# MAIN.net
KiCad netlist of a schematic drawn in Altium Designer
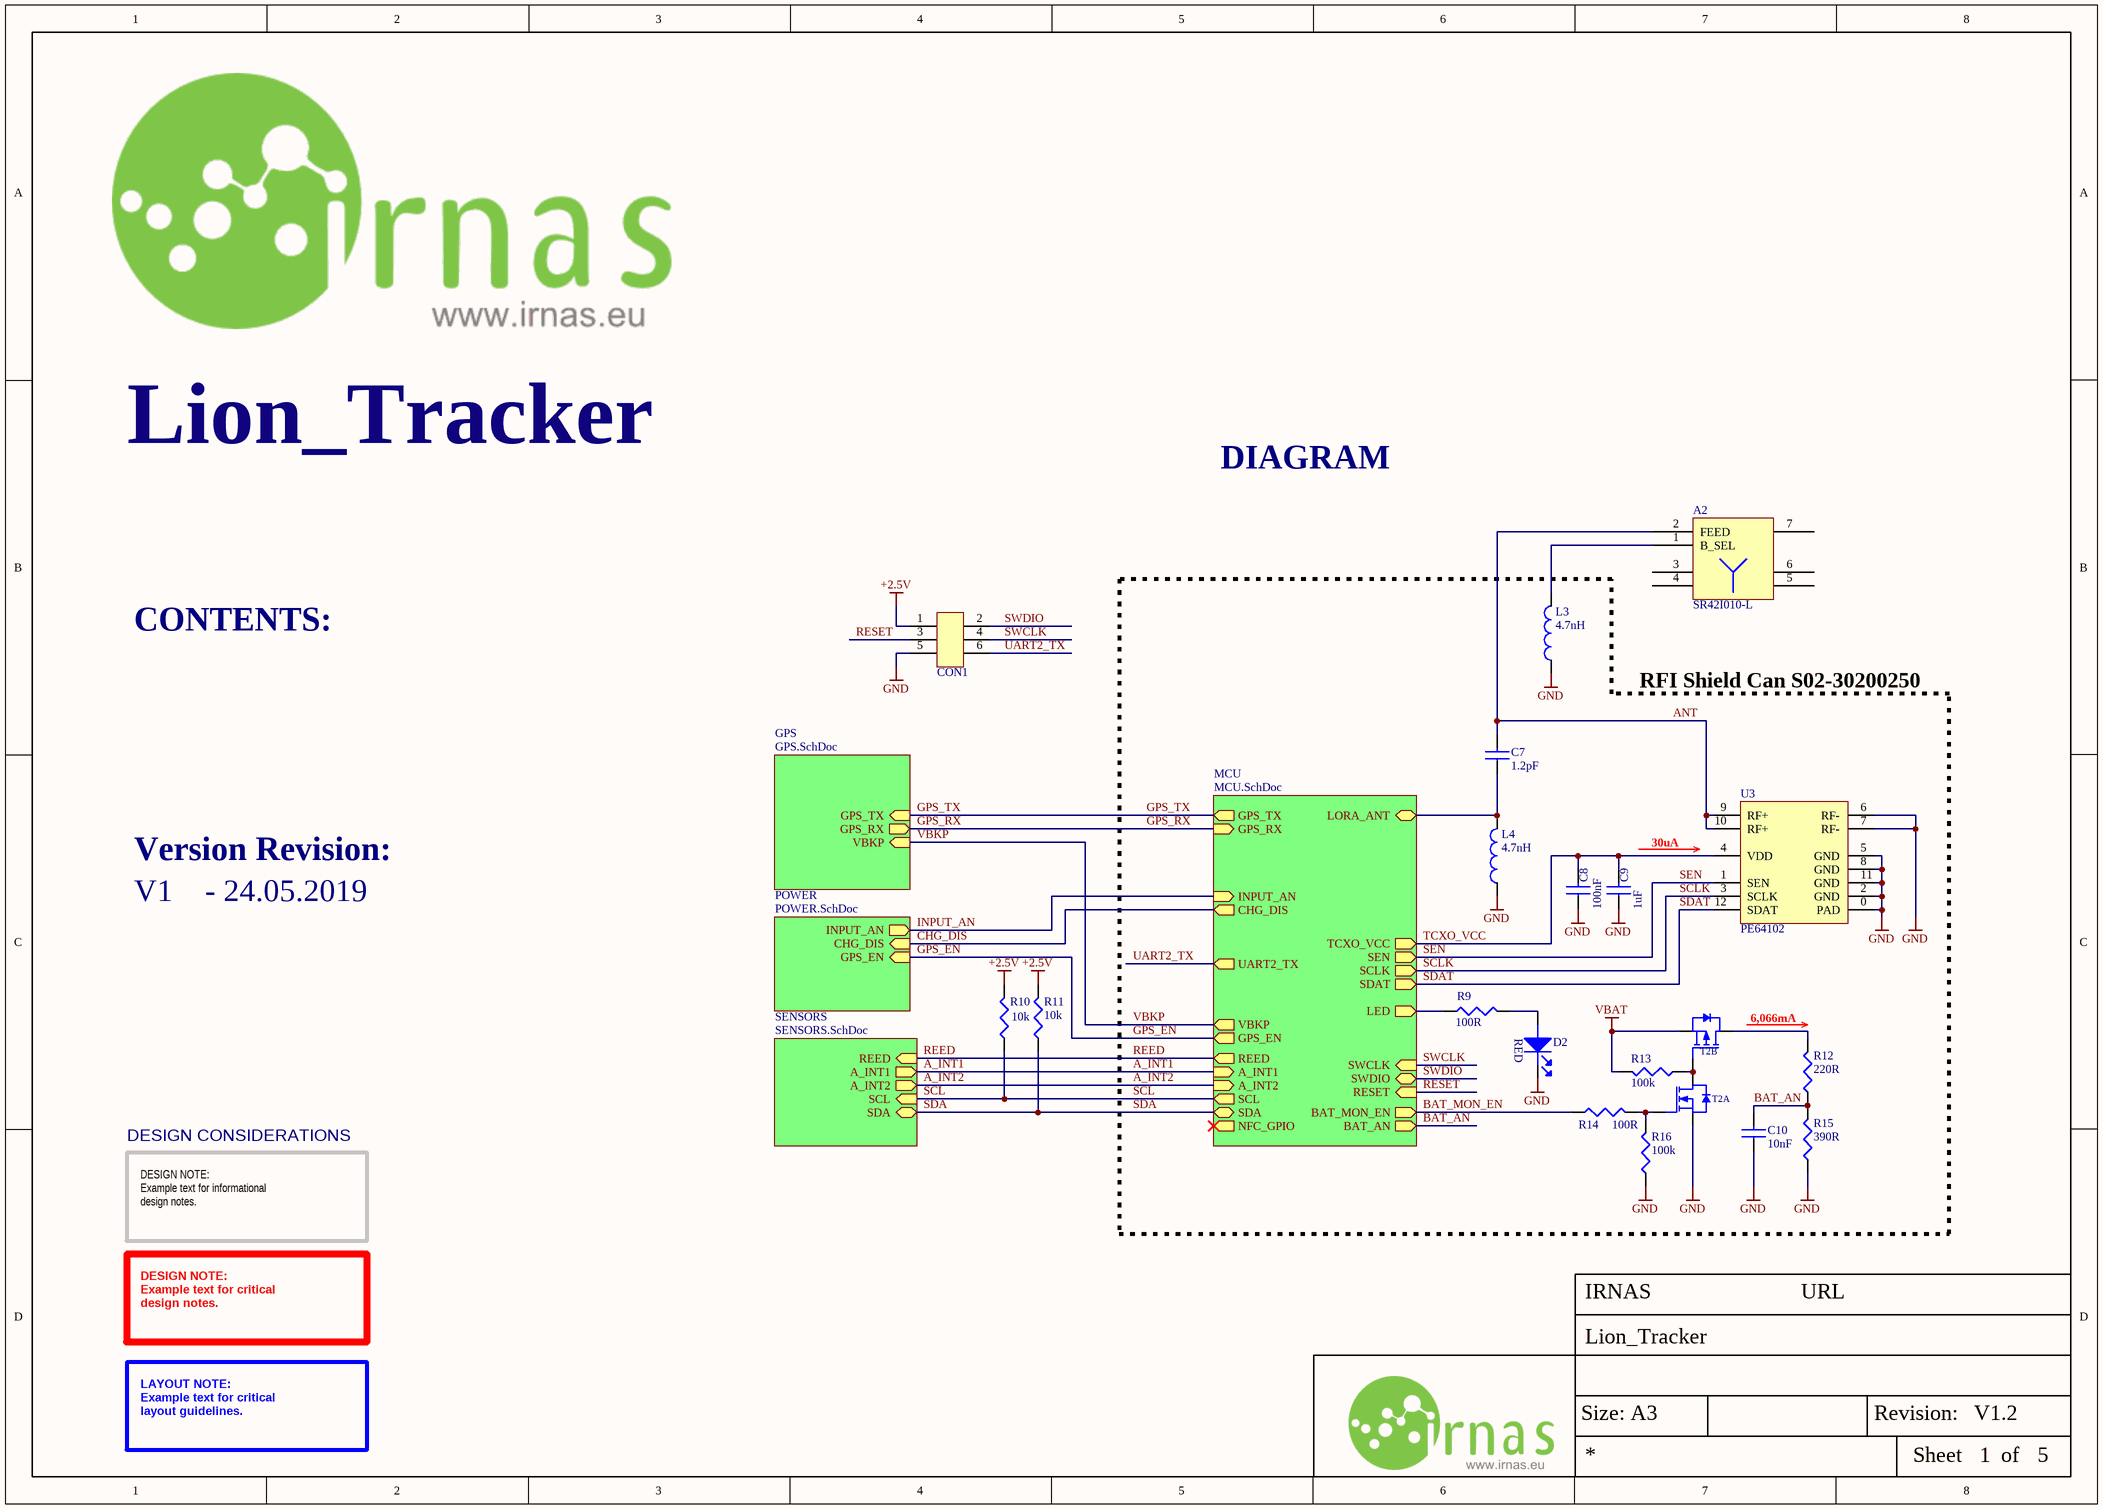
[diagram p0: MAIN.SchDoc]

(export (version "E")
  (design (tool "Eeschema 10.0.6"))
  (components
    (comp (ref "A2")
      (value "SR42I010-L")
      (footprint "SR42I010-L")
      (description "Antenna SMD -4dBi Gain 870MHz/928MHz Automotive 7-Pin SMD T/R")
      (fields (field (name "MANUFACTURER") "Antenova") (field (name "MANUFACTURER PART NUMBER") "SR42I010-R"))
      (libsource (lib "Passive") (part "ANT - SR42I010-L"))
    )
    (comp (ref "C7")
      (value "1.2pF")
      (footprint "CAP0402")
      (description "CAP CER 4700PF 50V X7R 0402")
      (fields
        (field (name "MANUFACTURER") "KEMET")
        (field (name "MANUFACTURER PART NUMBER") "C0402C472K5RAC-TU")
      )
      (libsource (lib "Passive") (part "C - 4.7nF/0402"))
    )
    (comp (ref "C8")
      (value "100nF")
      (footprint "CAP0402")
      (fields
        (field (name "MANUFACTURER") "Multicomp")
        (field (name "MANUFACTURER PART NUMBER") "MC0402X104J160CT")
        (field (name "TOLERANCE") "5%")
      )
      (libsource (lib "Passive") (part "C - 100nF/0402"))
    )
    (comp (ref "C9")
      (value "1uF")
      (footprint "CAP0402")
      (description "CAP CER 1UF 10V 20% X5R 0402")
      (fields
        (field (name "MANUFACTURER") "Murata")
        (field (name "MANUFACTURER PART NUMBER") "GRM155R61A105ME15D")
      )
      (libsource (lib "Passive") (part "C - 1uF/0402"))
    )
    (comp (ref "C10")
      (value "10nF")
      (footprint "CAP0402")
      (description "CAP CER 10000PF 16V X7R 0402")
      (fields
        (field (name "MANUFACTURER") "Murata")
        (field (name "MANUFACTURER PART NUMBER") "GRM155R71C103KA01D")
      )
      (libsource (lib "Passive") (part "C - 10nF/0402"))
    )
    (comp (ref "CON1")
      (value "Tag connect")
      (footprint "TC2030-IDC-NL")
      (libsource (lib "Connectors") (part "tag connecot 6 pin"))
    )
    (comp (ref "D2")
      (value "LED RED")
      (footprint "LED0603")
      (description "BROADCOM LIMITED - HSMS-C190 - LED, RED, 10MCD, 626NM")
      (fields
        (field (name "MANUFACTURER") "BROADCOM LIMITED")
        (field (name "MANUFACTURER PART NUMBER") "HSMS-C190")
      )
      (libsource (lib "Active") (part "LED - LED RED"))
    )
    (comp (ref "L3")
      (value "4.7nH")
      (footprint "IND0402")
      (description "Inductor RF Chip Multi-Layer 4.3nH 0.3nH 100MHz 8Q-Factor Air 300mA 210mOhm DCR 0402 Paper T/R")
      (fields
        (field (name "MANUFACTURER") "Murata")
        (field (name "MANUFACTURER PART NUMBER") "LQG15HN4N3S02D")
      )
      (libsource (lib "Passive") (part "L - 4.3nH/0402"))
    )
    (comp (ref "L4")
      (value "4.7nH")
      (footprint "IND0402")
      (description "Inductor RF Chip Multi-Layer 4.3nH 0.3nH 100MHz 8Q-Factor Air 300mA 210mOhm DCR 0402 Paper T/R")
      (fields
        (field (name "MANUFACTURER") "Murata")
        (field (name "MANUFACTURER PART NUMBER") "LQG15HN4N3S02D")
      )
      (libsource (lib "Passive") (part "L - 4.3nH/0402"))
    )
    (comp (ref "R9")
      (value "100R")
      (footprint "RES0402")
      (fields
        (field (name "MANUFACTURER") "Multicomp")
        (field (name "MANUFACTURER PART NUMBER") "MCMR04X1000FTL")
        (field (name "TOLERANCE") "1%")
      )
      (libsource (lib "Passive") (part "R - 100R/0402"))
    )
    (comp (ref "R10")
      (value "10k")
      (footprint "RES0402")
      (fields
        (field (name "MANUFACTURER") "Multicomp")
        (field (name "MANUFACTURER PART NUMBER") "MCWR04X1002FTL")
        (field (name "TOLERANCE") "1%")
      )
      (libsource (lib "Passive") (part "R - 10k/0402"))
    )
    (comp (ref "R11")
      (value "10k")
      (footprint "RES0402")
      (fields
        (field (name "MANUFACTURER") "Multicomp")
        (field (name "MANUFACTURER PART NUMBER") "MCWR04X1002FTL")
        (field (name "TOLERANCE") "1%")
      )
      (libsource (lib "Passive") (part "R - 10k/0402"))
    )
    (comp (ref "R12")
      (value "220R")
      (footprint "RES0402")
      (description "SMD Chip Resistor, 0402 [1005 Metric], 220 ohm, CRCW e3 Series, 50 V, Thick Film, 63 mW")
      (fields (field (name "MANUFACTURER") "Multicomp") (field (name "IRNAS PART NO.") "/"))
      (libsource (lib "Passive") (part "R - 220R/0402"))
    )
    (comp (ref "R13")
      (value "100k")
      (footprint "RES0402")
      (description "MULTICOMP   MCWR04X1003FTL   RES, THICK FILM, 100KOHM, 1%, 0.0625W")
      (fields
        (field (name "MANUFACTURER") "Multicomp")
        (field (name "MANUFACTURER PART NUMBER") "MCWR04X1003FTL")
      )
      (libsource (lib "Passive") (part "R - 100k/0402"))
    )
    (comp (ref "R14")
      (value "100R")
      (footprint "RES0402")
      (fields
        (field (name "MANUFACTURER") "Multicomp")
        (field (name "MANUFACTURER PART NUMBER") "MCMR04X1000FTL")
        (field (name "TOLERANCE") "1%")
      )
      (libsource (lib "Passive") (part "R - 100R/0402"))
    )
    (comp (ref "R15")
      (value "390R")
      (footprint "RES0402")
      (description "SMD Chip Resistor, 0402 [1005 Metric], 390 ohm, MCWR Series, 50 V, Thick Film, 62.5 mW")
      (fields (field (name "MANUFACTURER") "Multicomp") (field (name "IRNAS PART NO.") "/"))
      (libsource (lib "Passive") (part "R - 390R/0402"))
    )
    (comp (ref "R16")
      (value "100k")
      (footprint "RES0402")
      (description "MULTICOMP   MCWR04X1003FTL   RES, THICK FILM, 100KOHM, 1%, 0.0625W")
      (fields
        (field (name "MANUFACTURER") "Multicomp")
        (field (name "MANUFACTURER PART NUMBER") "MCWR04X1003FTL")
      )
      (libsource (lib "Passive") (part "R - 100k/0402"))
    )
    (comp (ref "T2")
      (value "VT6M1T2CR")
      (footprint "VMT6")
      (description "Dual MOSFET, N and P Channel, 100 mA, 20 V, 2.5 ohm, 4.5 V, 1 V")
      (fields (field (name "AUTHOR") "Ciril Golob"))
      (libsource (lib "Active") (part "T_M - VT6M1T2CR"))
    )
    (comp (ref "U3")
      (value "PE64102")
      (footprint "QFN-12")
      (description "RF IC Digitally Tunable Capacitor General Purpose 100MHz ~ 3GHz SPI Interface 12-QFN (2x2)")
      (fields (field (name "MANUFACTURER") "u-blox") (field (name "MANUFACTURER PART NUMBER") "MAX-M8Q-0"))
      (libsource (lib "Active") (part "RF - PE64102"))
    )
  )
  (nets
    (net (code "1") (name "+2.5V") (class "Default")
      (node (ref "CON1") (pin "1") (pinfunction "1_1") (pintype "open_collector"))
      (node (ref "R10") (pin "2") (pinfunction "2_2") (pintype "passive"))
      (node (ref "R11") (pin "2") (pinfunction "2_2") (pintype "passive"))
    )
    (net (code "2") (name "/ANT") (class "Default")
      (node (ref "A2") (pin "2") (pinfunction "FEED_2") (pintype "passive"))
      (node (ref "C7") (pin "2") (pinfunction "2_2") (pintype "passive"))
      (node (ref "U3") (pin "10") (pinfunction "RF+_10") (pintype "passive"))
      (node (ref "U3") (pin "9") (pinfunction "RF+_9") (pintype "passive"))
    )
    (net (code "5") (name "/BAT_AN") (class "Default")
      (node (ref "C10") (pin "2") (pinfunction "2_2") (pintype "passive"))
      (node (ref "R12") (pin "1") (pinfunction "1_1") (pintype "passive"))
      (node (ref "R15") (pin "2") (pinfunction "2_2") (pintype "passive"))
    )
    (net (code "6") (name "/BAT_MON_EN") (class "Default")
      (node (ref "R14") (pin "1") (pinfunction "1_1") (pintype "passive"))
    )
    (net (code "12") (name "/LED") (class "Default")
      (node (ref "R9") (pin "1") (pinfunction "1_1") (pintype "passive"))
    )
    (net (code "13") (name "/LORA_ANT") (class "Default")
      (node (ref "C7") (pin "1") (pinfunction "1_1") (pintype "passive"))
      (node (ref "L4") (pin "2") (pinfunction "2_2") (pintype "passive"))
    )
    (net (code "16") (name "/RESET") (class "Default")
      (node (ref "CON1") (pin "3") (pinfunction "3_3") (pintype "open_collector"))
    )
    (net (code "17") (name "/SCL") (class "Default")
      (node (ref "R10") (pin "1") (pinfunction "1_1") (pintype "passive"))
    )
    (net (code "18") (name "/SCLK") (class "Default")
      (node (ref "U3") (pin "3") (pinfunction "SCLK_3") (pintype "passive"))
    )
    (net (code "19") (name "/SDA") (class "Default")
      (node (ref "R11") (pin "1") (pinfunction "1_1") (pintype "passive"))
    )
    (net (code "20") (name "/SDAT") (class "Default")
      (node (ref "U3") (pin "12") (pinfunction "SDAT_12") (pintype "passive"))
    )
    (net (code "21") (name "/SEN") (class "Default")
      (node (ref "U3") (pin "1") (pinfunction "SEN_1") (pintype "passive"))
    )
    (net (code "22") (name "/SWCLK") (class "Default")
      (node (ref "CON1") (pin "4") (pinfunction "4_4") (pintype "open_collector"))
    )
    (net (code "23") (name "/SWDIO") (class "Default")
      (node (ref "CON1") (pin "2") (pinfunction "2_2") (pintype "open_collector"))
    )
    (net (code "24") (name "/TCXO_VCC") (class "Default")
      (node (ref "C8") (pin "2") (pinfunction "2_2") (pintype "passive"))
      (node (ref "C9") (pin "2") (pinfunction "2_2") (pintype "passive"))
      (node (ref "U3") (pin "4") (pinfunction "VDD_4") (pintype "passive"))
    )
    (net (code "25") (name "/UART2_TX") (class "Default")
      (node (ref "CON1") (pin "6") (pinfunction "6_6") (pintype "passive"))
    )
    (net (code "27") (name "GND") (class "Default")
      (node (ref "C10") (pin "1") (pinfunction "1_1") (pintype "passive"))
      (node (ref "C8") (pin "1") (pinfunction "1_1") (pintype "passive"))
      (node (ref "C9") (pin "1") (pinfunction "1_1") (pintype "passive"))
      (node (ref "CON1") (pin "5") (pinfunction "5_5") (pintype "open_collector"))
      (node (ref "D2") (pin "1") (pinfunction "cathode_1") (pintype "passive"))
      (node (ref "L3") (pin "1") (pinfunction "1_1") (pintype "passive"))
      (node (ref "L4") (pin "1") (pinfunction "1_1") (pintype "passive"))
      (node (ref "R15") (pin "1") (pinfunction "1_1") (pintype "passive"))
      (node (ref "R16") (pin "1") (pinfunction "1_1") (pintype "passive"))
      (node (ref "T2") (pin "1") (pinfunction "S1_1") (pintype "passive"))
      (node (ref "U3") (pin "0") (pinfunction "PAD_0") (pintype "passive"))
      (node (ref "U3") (pin "11") (pinfunction "GND_11") (pintype "passive"))
      (node (ref "U3") (pin "2") (pinfunction "GND_2") (pintype "passive"))
      (node (ref "U3") (pin "5") (pinfunction "GND_5") (pintype "passive"))
      (node (ref "U3") (pin "6") (pinfunction "RF-_6") (pintype "passive"))
      (node (ref "U3") (pin "7") (pinfunction "RF-_7") (pintype "passive"))
      (node (ref "U3") (pin "8") (pinfunction "GND_8") (pintype "passive"))
    )
    (net (code "28") (name "Net-(A2-B_SEL)") (class "Default")
      (node (ref "A2") (pin "1") (pinfunction "B_SEL_1") (pintype "passive"))
      (node (ref "L3") (pin "2") (pinfunction "2_2") (pintype "passive"))
    )
    (net (code "29") (name "Net-(D2-ANODE)") (class "Default")
      (node (ref "D2") (pin "2") (pinfunction "ANODE_2") (pintype "passive"))
      (node (ref "R9") (pin "2") (pinfunction "2_2") (pintype "passive"))
    )
    (net (code "30") (name "Net-(T2A-D1)") (class "Default")
      (node (ref "R13") (pin "1") (pinfunction "1_1") (pintype "passive"))
      (node (ref "T2") (pin "5") (pinfunction "G2_5") (pintype "passive"))
      (node (ref "T2") (pin "6") (pinfunction "D1_6") (pintype "passive"))
    )
    (net (code "31") (name "Net-(T2A-G1)") (class "Default")
      (node (ref "R14") (pin "2") (pinfunction "2_2") (pintype "passive"))
      (node (ref "R16") (pin "2") (pinfunction "2_2") (pintype "passive"))
      (node (ref "T2") (pin "2") (pinfunction "G1_2") (pintype "passive"))
    )
    (net (code "32") (name "Net-(T2B-D2)") (class "Default")
      (node (ref "R12") (pin "2") (pinfunction "2_2") (pintype "passive"))
      (node (ref "T2") (pin "3") (pinfunction "D2_3") (pintype "passive"))
    )
    (net (code "33") (name "VBAT") (class "Default")
      (node (ref "R13") (pin "2") (pinfunction "2_2") (pintype "passive"))
      (node (ref "T2") (pin "4") (pinfunction "S2_4") (pintype "passive"))
    )
    (net (code "34") (name "unconnected-(A2-Pad3)") (class "Default")
      (node (ref "A2") (pin "3") (pintype "passive"))
    )
    (net (code "35") (name "unconnected-(A2-Pad4)") (class "Default")
      (node (ref "A2") (pin "4") (pintype "passive"))
    )
    (net (code "36") (name "unconnected-(A2-Pad5)") (class "Default")
      (node (ref "A2") (pin "5") (pintype "passive"))
    )
    (net (code "37") (name "unconnected-(A2-Pad6)") (class "Default")
      (node (ref "A2") (pin "6") (pintype "passive"))
    )
    (net (code "38") (name "unconnected-(A2-Pad7)") (class "Default")
      (node (ref "A2") (pin "7") (pintype "passive"))
    )
  )
)
